# EMS_Bus.net
KiCad netlist of a schematic drawn in Altium Designer
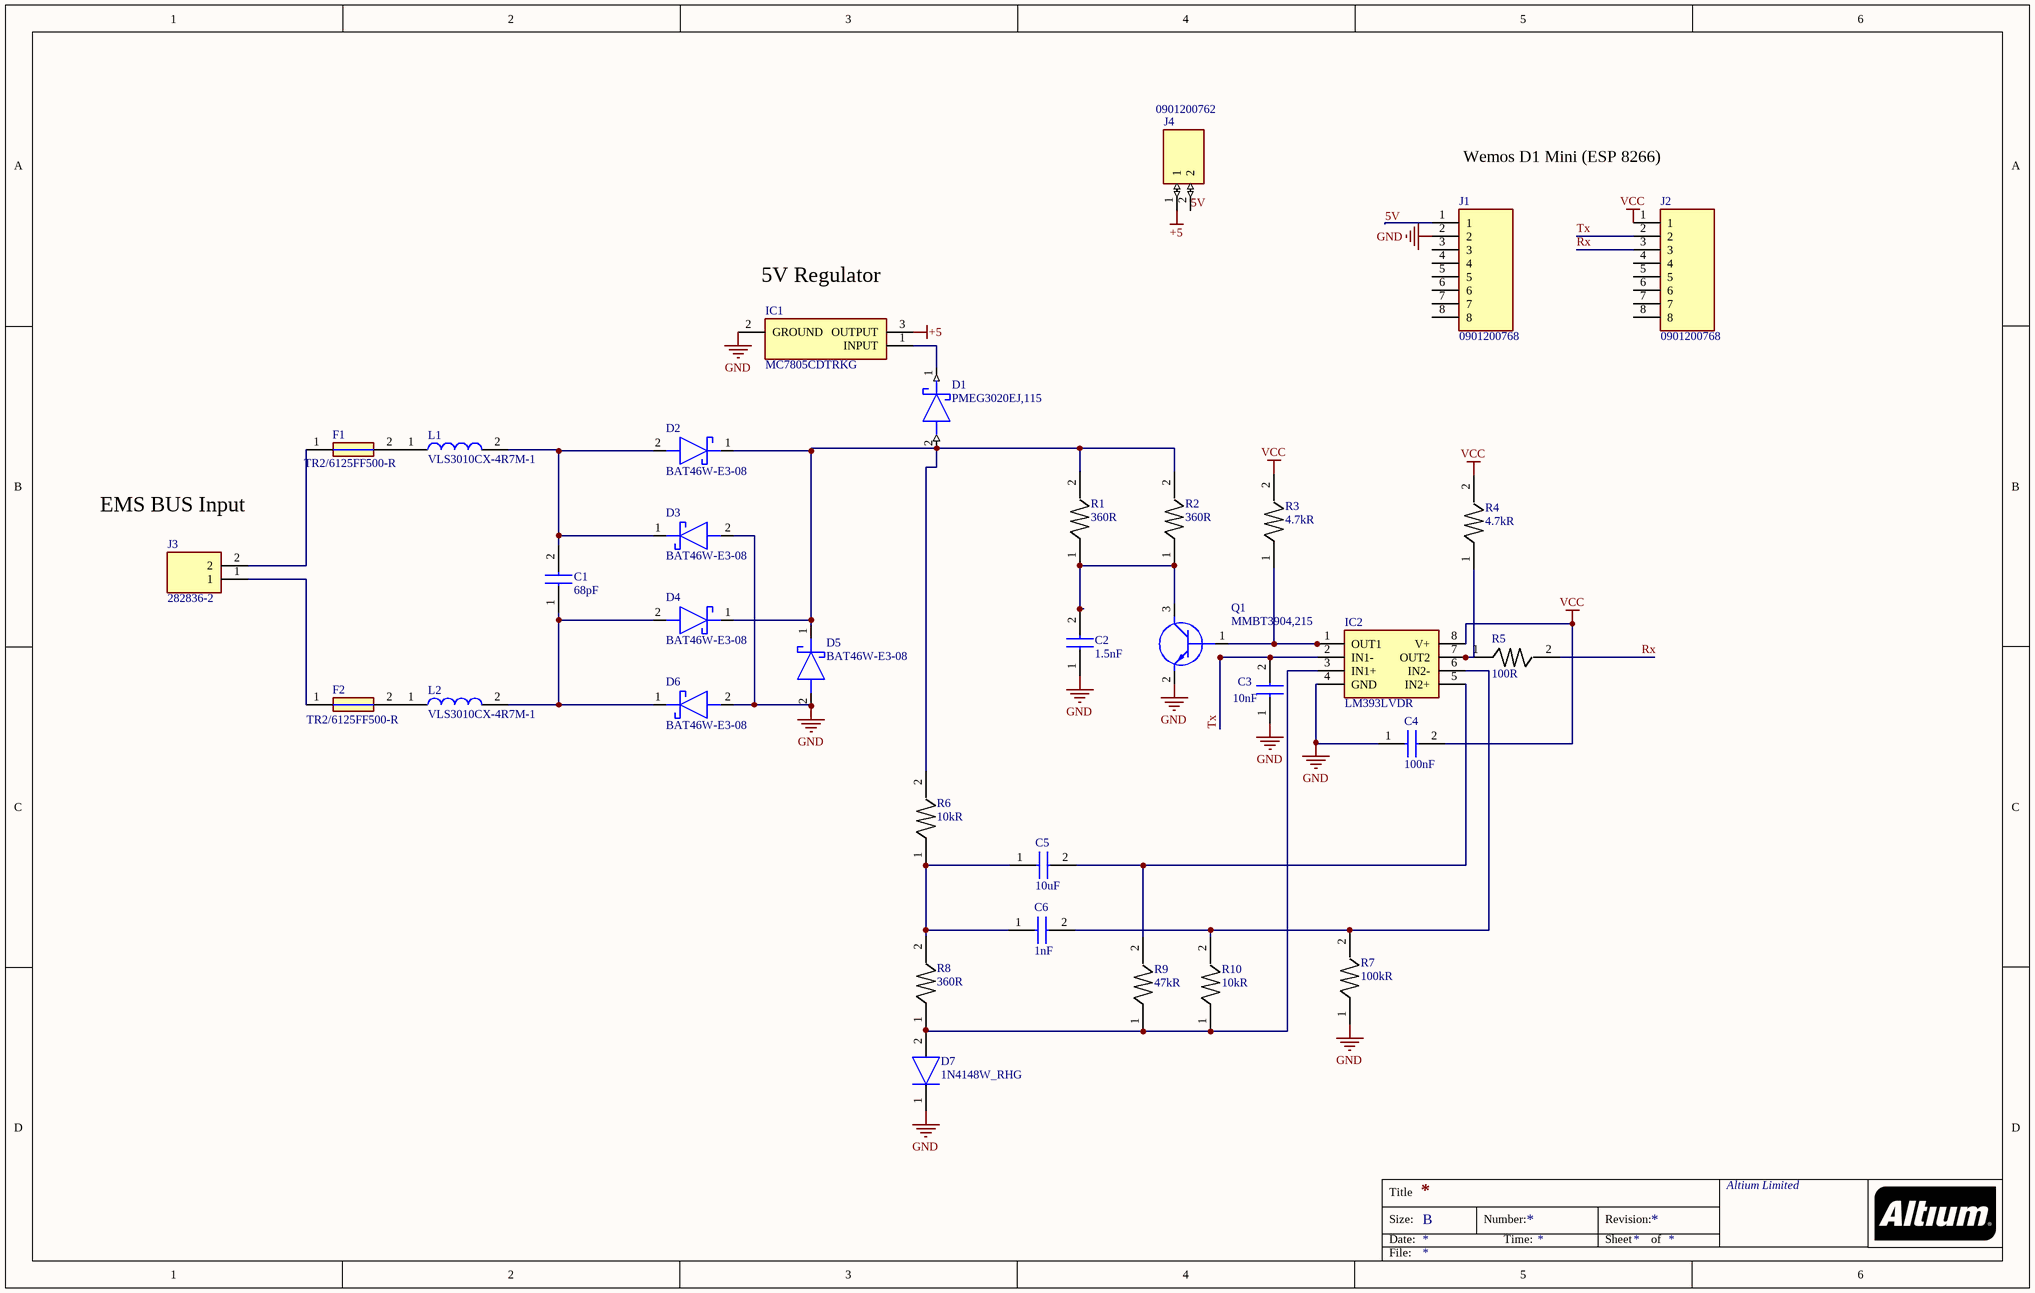
[diagram p0: EMS_Bus.SchDoc]

(export (version "E")
  (design (tool "Eeschema 10.0.6"))
  (components
    (comp (ref "C1")
      (value "885012007056")
      (footprint "SamacSys:CAPC2012X70N")
      (description "Capacitor")
      (fields
        (field (name "MANUFACTURER") "Wurth Electronics")
        (field (name "CAPACITANCE") "68pF")
        (field (name "TOLERANCE") "5%")
      )
      (libsource (lib "SamacSys") (part "885012007056"))
    )
    (comp (ref "C2")
      (value "885012207087")
      (footprint "SamacSys:CAPC2012X90N")
      (description "Capacitor")
      (fields
        (field (name "MOUSER PART NUMBER") "710-885012207087")
        (field (name "MANUFACTURER") "Wurth Electronics")
        (field (name "CAPACITANCE") "1.5nF")
      )
      (libsource (lib "SamacSys") (part "885012207087"))
    )
    (comp (ref "C3")
      (value "885012207092")
      (footprint "SamacSys:CAPC2012X90N")
      (description "Capacitor")
      (fields
        (field (name "MOUSER PART NUMBER") "710-885012207092")
        (field (name "MANUFACTURER") "Wurth Electronics")
        (field (name "CAPACITANCE") "10nF")
      )
      (libsource (lib "SamacSys") (part "885012207092"))
    )
    (comp (ref "C4")
      (value "885012207098")
      (footprint "SamacSys:CAPC2012X90N")
      (description "Capacitor")
      (fields
        (field (name "MOUSER PART NUMBER") "710-885012207098")
        (field (name "MANUFACTURER") "Wurth Electronics")
        (field (name "CAPACITANCE") "100nF")
      )
      (libsource (lib "SamacSys") (part "885012207098"))
    )
    (comp (ref "C5")
      (value "885012107014")
      (footprint "SamacSys:CAPC2012X135N")
      (description "Capacitor")
      (fields
        (field (name "MOUSER PART NUMBER") "710-885012107014")
        (field (name "MANUFACTURER") "Wurth Electronics")
        (field (name "CAPACITANCE") "10uF")
      )
      (libsource (lib "SamacSys") (part "885012107014"))
    )
    (comp (ref "C6")
      (value "885012007063")
      (footprint "SamacSys:CAPC2012X90N")
      (description "Capacitor")
      (fields
        (field (name "MOUSER PART NUMBER") "710-885012007063")
        (field (name "MANUFACTURER") "Wurth Electronics")
        (field (name "CAPACITANCE") "1nF")
      )
      (libsource (lib "SamacSys") (part "885012007063"))
    )
    (comp (ref "D1")
      (value "PMEG3020EJ,115")
      (footprint "SamacSys:SODFL2512X80N")
      (description "Schottky Diode")
      (fields (field (name "MOUSER PART NUMBER") "771-PMEG3020EJ-T/R"))
      (libsource (lib "SamacSys") (part "PMEG3020EJ,115"))
    )
    (comp (ref "D2")
      (value "BAT46W-E3-08")
      (footprint "SamacSys:SOD3716X135N")
      (description "Schottky Diode")
      (fields
        (field (name "MANUFACTURER_PART_NUMBER") "BAT46W-E3-08")
        (field (name "MOUSER PART NUMBER") "78-BAT46W-E3-08")
      )
      (libsource (lib "SamacSys") (part "BAT46W-E3-08"))
    )
    (comp (ref "D3")
      (value "BAT46W-E3-08")
      (footprint "SamacSys:SOD3716X135N")
      (description "Schottky Diode")
      (fields
        (field (name "MANUFACTURER_PART_NUMBER") "BAT46W-E3-08")
        (field (name "MOUSER PART NUMBER") "78-BAT46W-E3-08")
      )
      (libsource (lib "SamacSys") (part "BAT46W-E3-08"))
    )
    (comp (ref "D4")
      (value "BAT46W-E3-08")
      (footprint "SamacSys:SOD3716X135N")
      (description "Schottky Diode")
      (fields
        (field (name "MANUFACTURER_PART_NUMBER") "BAT46W-E3-08")
        (field (name "MOUSER PART NUMBER") "78-BAT46W-E3-08")
      )
      (libsource (lib "SamacSys") (part "BAT46W-E3-08"))
    )
    (comp (ref "D5")
      (value "BAT46W-E3-08")
      (footprint "SamacSys:SOD3716X135N")
      (description "Schottky Diode")
      (fields
        (field (name "MANUFACTURER_PART_NUMBER") "BAT46W-E3-08")
        (field (name "MOUSER PART NUMBER") "78-BAT46W-E3-08")
      )
      (libsource (lib "SamacSys") (part "BAT46W-E3-08"))
    )
    (comp (ref "D6")
      (value "BAT46W-E3-08")
      (footprint "SamacSys:SOD3716X135N")
      (description "Schottky Diode")
      (fields
        (field (name "MANUFACTURER_PART_NUMBER") "BAT46W-E3-08")
        (field (name "MOUSER PART NUMBER") "78-BAT46W-E3-08")
      )
      (libsource (lib "SamacSys") (part "BAT46W-E3-08"))
    )
    (comp (ref "D7")
      (value "1N4148W_RHG")
      (footprint "SamacSys:1N4148WRHG")
      (description "Diode")
      (fields
        (field (name "MANUFACTURER_PART_NUMBER") "1N4148W RHG")
        (field (name "MOUSER PART NUMBER") "821-1N4148WRHG")
      )
      (libsource (lib "SamacSys") (part "1N4148W_RHG"))
    )
    (comp (ref "F1")
      (value "TR2_6125FF500-R")
      (footprint "SamacSys:FUSC6127X287N")
      (description "Fuse")
      (fields
        (field (name "MANUFACTURER_PART_NUMBER") "TR2/6125FF500-R")
        (field (name "MOUSER PART NUMBER") "504-TR2/6125FF500-R")
        (field (name "MANUFACTURER PART NUMBER") "TR2/6125FF500-R")
      )
      (libsource (lib "SamacSys") (part "TR2_6125FF500-R"))
    )
    (comp (ref "F2")
      (value "TR2_6125FF500-R")
      (footprint "SamacSys:FUSC6127X287N")
      (description "Fuse")
      (fields
        (field (name "MANUFACTURER_PART_NUMBER") "TR2/6125FF500-R")
        (field (name "MOUSER PART NUMBER") "504-TR2/6125FF500-R")
        (field (name "MANUFACTURER PART NUMBER") "TR2/6125FF500-R")
      )
      (libsource (lib "SamacSys") (part "TR2_6125FF500-R"))
    )
    (comp (ref "IC1")
      (value "MC7805CDTRKG")
      (footprint "SamacSys:MJD1221G")
      (description "Integrated Circuit")
      (fields
        (field (name "MOUSER PART NUMBER") "863-MC7805CDTRKG")
        (field (name "MANUFACTURER") "ON Semiconductor")
        (field (name "MANUFACTURER PART NUMBER") "MC7805CDTRKG")
      )
      (libsource (lib "SamacSys") (part "MC7805CDTRKG"))
    )
    (comp (ref "IC2")
      (value "LM393LVDR")
      (footprint "SamacSys:SOIC127P600X175-8N")
      (description "Integrated Circuit")
      (fields
        (field (name "MOUSER PART NUMBER") "595-LM393LVDR")
        (field (name "MANUFACTURER") "Texas Instruments")
        (field (name "MANUFACTURER PART NUMBER") "LM393LVDR")
      )
      (libsource (lib "SamacSys") (part "LM393LVDR"))
    )
    (comp (ref "J1")
      (value "0901200768")
      (footprint "SamacSys:HDRV8W65P0X254_1X8_2010X249X560P")
      (description "Connector")
      (libsource (lib "SamacSys") (part "0901200768"))
    )
    (comp (ref "J2")
      (value "0901200768")
      (footprint "SamacSys:HDRV8W65P0X254_1X8_2010X249X560P")
      (description "Connector")
      (libsource (lib "SamacSys") (part "0901200768"))
    )
    (comp (ref "J3")
      (value "282836-2")
      (footprint "2828362")
      (description "Connector")
      (fields (field (name "MOUSER PART NUMBER") "571-2828362"))
      (libsource (lib "SamacSys") (part "282836-2"))
    )
    (comp (ref "J4")
      (value "0901200762")
      (footprint "SamacSys:HDRV2W65P0X254_1X2_508X254X925P")
      (description "Connector")
      (libsource (lib "SamacSys") (part "0901200762"))
    )
    (comp (ref "L1")
      (value "VLS3010CX-4R7M-1")
      (footprint "SamacSys:INDPM3030X100N")
      (description "Inductor")
      (fields
        (field (name "MOUSER PART NUMBER") "810-VLS3010CX-4R7M-1")
        (field (name "MANUFACTURER") "TDK")
        (field (name "MANUFACTURER PART NUMBER") "VLS3010CX-4R7M-1")
      )
      (libsource (lib "SamacSys") (part "VLS3010CX-4R7M-1"))
    )
    (comp (ref "L2")
      (value "VLS3010CX-4R7M-1")
      (footprint "SamacSys:INDPM3030X100N")
      (description "Inductor")
      (fields
        (field (name "MOUSER PART NUMBER") "810-VLS3010CX-4R7M-1")
        (field (name "MANUFACTURER") "TDK")
        (field (name "MANUFACTURER PART NUMBER") "VLS3010CX-4R7M-1")
      )
      (libsource (lib "SamacSys") (part "VLS3010CX-4R7M-1"))
    )
    (comp (ref "Q1")
      (value "MMBT3904,215")
      (footprint "SamacSys:SOT95P230X110-3N")
      (description "Transistor BJT NPN")
      (fields
        (field (name "MANUFACTURER_PART_NUMBER") "MMBT3904,215")
        (field (name "MOUSER PART NUMBER") "771-MMBT3904T/R")
        (field (name "MANUFACTURER") "Nexperia")
      )
      (libsource (lib "SamacSys") (part "MMBT3904,215"))
    )
    (comp (ref "R1")
      (value "RC0805FR-07360RL")
      (footprint "SamacSys:RESC2012X60N")
      (description "Resistor")
      (fields
        (field (name "MOUSER PART NUMBER") "603-RC0805FR-07360RL")
        (field (name "MANUFACTURER") "Yageo")
        (field (name "RESISTANCE") "360R")
      )
      (libsource (lib "SamacSys") (part "RC0805FR-07360RL"))
    )
    (comp (ref "R2")
      (value "RC0805FR-07360RL")
      (footprint "SamacSys:RESC2012X60N")
      (description "Resistor")
      (fields
        (field (name "MOUSER PART NUMBER") "603-RC0805FR-07360RL")
        (field (name "MANUFACTURER") "Yageo")
        (field (name "RESISTANCE") "360R")
      )
      (libsource (lib "SamacSys") (part "RC0805FR-07360RL"))
    )
    (comp (ref "R3")
      (value "RC0805FR-074K7L")
      (footprint "SamacSys:RESC2012X60N")
      (description "Resistor")
      (fields
        (field (name "MOUSER PART NUMBER") "603-RC0805FR-074K7L")
        (field (name "MANUFACTURER") "Yageo")
        (field (name "RESISTANCE") "4.7kR")
      )
      (libsource (lib "SamacSys") (part "RC0805FR-074K7L"))
    )
    (comp (ref "R4")
      (value "RC0805FR-074K7L")
      (footprint "SamacSys:RESC2012X60N")
      (description "Resistor")
      (fields
        (field (name "MOUSER PART NUMBER") "603-RC0805FR-074K7L")
        (field (name "MANUFACTURER") "Yageo")
        (field (name "RESISTANCE") "4.7kR")
      )
      (libsource (lib "SamacSys") (part "RC0805FR-074K7L"))
    )
    (comp (ref "R5")
      (value "RC0805FR-07100RL")
      (footprint "SamacSys:RESC2012X60N")
      (description "Resistor")
      (fields
        (field (name "MOUSER PART NUMBER") "603-RC0805FR-07100RL")
        (field (name "MANUFACTURER") "Yageo")
        (field (name "RESISTANCE") "100R")
      )
      (libsource (lib "SamacSys") (part "RC0805FR-07100RL"))
    )
    (comp (ref "R6")
      (value "RT0805FRE0710KL")
      (footprint "SamacSys:RESC2012X60N")
      (description "Resistor")
      (fields
        (field (name "MOUSER PART NUMBER") "603-RT0805FRE0710KL")
        (field (name "MANUFACTURER") "Yageo")
        (field (name "RESISTANCE") "10kR")
      )
      (libsource (lib "SamacSys") (part "RT0805FRE0710KL"))
    )
    (comp (ref "R7")
      (value "RC0805FR-07100KL")
      (footprint "SamacSys:RESC2012X60N")
      (description "Resistor")
      (fields
        (field (name "MOUSER PART NUMBER") "603-RC0805FR-07100KL")
        (field (name "MANUFACTURER") "Yageo")
        (field (name "RESISTANCE") "100kR")
      )
      (libsource (lib "SamacSys") (part "RC0805FR-07100KL"))
    )
    (comp (ref "R8")
      (value "RC0805FR-07360RL")
      (footprint "SamacSys:RESC2012X60N")
      (description "Resistor")
      (fields
        (field (name "MOUSER PART NUMBER") "603-RC0805FR-07360RL")
        (field (name "MANUFACTURER") "Yageo")
        (field (name "RESISTANCE") "360R")
      )
      (libsource (lib "SamacSys") (part "RC0805FR-07360RL"))
    )
    (comp (ref "R9")
      (value "RT0805FRE0747KL")
      (footprint "SamacSys:RESC2012X60N")
      (description "Resistor")
      (fields
        (field (name "MOUSER PART NUMBER") "603-RT0805FRE0747KL")
        (field (name "MANUFACTURER") "Yageo")
        (field (name "RESISTANCE") "47kR")
      )
      (libsource (lib "SamacSys") (part "RT0805FRE0747KL"))
    )
    (comp (ref "R10")
      (value "RT0805FRE0710KL")
      (footprint "SamacSys:RESC2012X60N")
      (description "Resistor")
      (fields
        (field (name "MOUSER PART NUMBER") "603-RT0805FRE0710KL")
        (field (name "MANUFACTURER") "Yageo")
        (field (name "RESISTANCE") "10kR")
      )
      (libsource (lib "SamacSys") (part "RT0805FRE0710KL"))
    )
  )
  (nets
    (net (code "1") (name "+5") (class "Default")
      (node (ref "IC1") (pin "3") (pinfunction "OUTPUT_3") (pintype "passive"))
      (node (ref "J4") (pin "1") (pinfunction "1_1") (pintype "bidirectional"))
    )
    (net (code "2") (name "/5V") (class "Default")
      (node (ref "J1") (pin "1") (pinfunction "1_1") (pintype "passive"))
      (node (ref "J4") (pin "2") (pinfunction "2_2") (pintype "bidirectional"))
    )
    (net (code "3") (name "/Rx") (class "Default")
      (node (ref "J2") (pin "3") (pinfunction "3_3") (pintype "passive"))
      (node (ref "R5") (pin "2") (pinfunction "2_2") (pintype "passive"))
    )
    (net (code "4") (name "/Tx") (class "Default")
      (node (ref "C3") (pin "2") (pinfunction "2_2") (pintype "passive"))
      (node (ref "IC2") (pin "2") (pinfunction "IN1-_2") (pintype "passive"))
      (node (ref "J2") (pin "2") (pinfunction "2_2") (pintype "passive"))
    )
    (net (code "5") (name "GND") (class "Default")
      (node (ref "C2") (pin "1") (pinfunction "1_1") (pintype "passive"))
      (node (ref "C3") (pin "1") (pinfunction "1_1") (pintype "passive"))
      (node (ref "C4") (pin "1") (pinfunction "1_1") (pintype "passive"))
      (node (ref "D3") (pin "2") (pinfunction "A_2") (pintype "passive"))
      (node (ref "D5") (pin "2") (pinfunction "A_2") (pintype "passive"))
      (node (ref "D6") (pin "2") (pinfunction "A_2") (pintype "passive"))
      (node (ref "D7") (pin "1") (pinfunction "K_1") (pintype "passive"))
      (node (ref "IC1") (pin "2") (pinfunction "GROUND_2") (pintype "passive"))
      (node (ref "IC2") (pin "4") (pinfunction "GND_4") (pintype "passive"))
      (node (ref "J1") (pin "2") (pinfunction "2_2") (pintype "passive"))
      (node (ref "Q1") (pin "2") (pinfunction "E_2") (pintype "passive"))
      (node (ref "R7") (pin "1") (pinfunction "1_1") (pintype "passive"))
    )
    (net (code "6") (name "Net-(C5-Pad1)") (class "Default")
      (node (ref "C5") (pin "1") (pinfunction "1_1") (pintype "passive"))
      (node (ref "C6") (pin "1") (pinfunction "1_1") (pintype "passive"))
      (node (ref "R6") (pin "1") (pinfunction "1_1") (pintype "passive"))
      (node (ref "R8") (pin "2") (pinfunction "2_2") (pintype "passive"))
    )
    (net (code "7") (name "Net-(D1-A)") (class "Default")
      (node (ref "D1") (pin "2") (pinfunction "A_2") (pintype "input"))
      (node (ref "D2") (pin "1") (pinfunction "K_1") (pintype "passive"))
      (node (ref "D4") (pin "1") (pinfunction "K_1") (pintype "passive"))
      (node (ref "D5") (pin "1") (pinfunction "K_1") (pintype "passive"))
      (node (ref "R1") (pin "2") (pinfunction "2_2") (pintype "passive"))
      (node (ref "R2") (pin "2") (pinfunction "2_2") (pintype "passive"))
      (node (ref "R6") (pin "2") (pinfunction "2_2") (pintype "passive"))
    )
    (net (code "8") (name "Net-(D1-K)") (class "Default")
      (node (ref "D1") (pin "1") (pinfunction "K_1") (pintype "output"))
      (node (ref "IC1") (pin "1") (pinfunction "INPUT_1") (pintype "passive"))
    )
    (net (code "9") (name "Net-(D2-A)") (class "Default")
      (node (ref "C1") (pin "2") (pinfunction "2_2") (pintype "passive"))
      (node (ref "D2") (pin "2") (pinfunction "A_2") (pintype "passive"))
      (node (ref "D3") (pin "1") (pinfunction "K_1") (pintype "passive"))
      (node (ref "L1") (pin "2") (pinfunction "2_2") (pintype "passive"))
    )
    (net (code "10") (name "Net-(D4-A)") (class "Default")
      (node (ref "C1") (pin "1") (pinfunction "1_1") (pintype "passive"))
      (node (ref "D4") (pin "2") (pinfunction "A_2") (pintype "passive"))
      (node (ref "D6") (pin "1") (pinfunction "K_1") (pintype "passive"))
      (node (ref "L2") (pin "2") (pinfunction "2_2") (pintype "passive"))
    )
    (net (code "11") (name "Net-(D7-A)") (class "Default")
      (node (ref "D7") (pin "2") (pinfunction "A_2") (pintype "passive"))
      (node (ref "IC2") (pin "3") (pinfunction "IN1+_3") (pintype "passive"))
      (node (ref "R10") (pin "1") (pinfunction "1_1") (pintype "passive"))
      (node (ref "R8") (pin "1") (pinfunction "1_1") (pintype "passive"))
      (node (ref "R9") (pin "1") (pinfunction "1_1") (pintype "passive"))
    )
    (net (code "12") (name "Net-(F1-Pad1)") (class "Default")
      (node (ref "F1") (pin "1") (pinfunction "1_1") (pintype "passive"))
      (node (ref "J3") (pin "2") (pinfunction "2_2") (pintype "passive"))
    )
    (net (code "13") (name "Net-(F1-Pad2)") (class "Default")
      (node (ref "F1") (pin "2") (pinfunction "2_2") (pintype "passive"))
      (node (ref "L1") (pin "1") (pinfunction "1_1") (pintype "passive"))
    )
    (net (code "14") (name "Net-(F2-Pad1)") (class "Default")
      (node (ref "F2") (pin "1") (pinfunction "1_1") (pintype "passive"))
      (node (ref "J3") (pin "1") (pinfunction "1_1") (pintype "passive"))
    )
    (net (code "15") (name "Net-(F2-Pad2)") (class "Default")
      (node (ref "F2") (pin "2") (pinfunction "2_2") (pintype "passive"))
      (node (ref "L2") (pin "1") (pinfunction "1_1") (pintype "passive"))
    )
    (net (code "16") (name "Net-(IC2-IN2+)") (class "Default")
      (node (ref "C5") (pin "2") (pinfunction "2_2") (pintype "passive"))
      (node (ref "IC2") (pin "5") (pinfunction "IN2+_5") (pintype "passive"))
      (node (ref "R9") (pin "2") (pinfunction "2_2") (pintype "passive"))
    )
    (net (code "17") (name "Net-(IC2-IN2-)") (class "Default")
      (node (ref "C6") (pin "2") (pinfunction "2_2") (pintype "passive"))
      (node (ref "IC2") (pin "6") (pinfunction "IN2-_6") (pintype "passive"))
      (node (ref "R10") (pin "2") (pinfunction "2_2") (pintype "passive"))
      (node (ref "R7") (pin "2") (pinfunction "2_2") (pintype "passive"))
    )
    (net (code "18") (name "Net-(IC2-OUT1)") (class "Default")
      (node (ref "IC2") (pin "1") (pinfunction "OUT1_1") (pintype "passive"))
      (node (ref "Q1") (pin "1") (pinfunction "B_1") (pintype "passive"))
      (node (ref "R3") (pin "1") (pinfunction "1_1") (pintype "passive"))
    )
    (net (code "19") (name "Net-(IC2-OUT2)") (class "Default")
      (node (ref "IC2") (pin "7") (pinfunction "OUT2_7") (pintype "passive"))
      (node (ref "R4") (pin "1") (pinfunction "1_1") (pintype "passive"))
      (node (ref "R5") (pin "1") (pinfunction "1_1") (pintype "passive"))
    )
    (net (code "20") (name "Net-(Q1-C)") (class "Default")
      (node (ref "C2") (pin "2") (pinfunction "2_2") (pintype "passive"))
      (node (ref "Q1") (pin "3") (pinfunction "C_3") (pintype "passive"))
      (node (ref "R1") (pin "1") (pinfunction "1_1") (pintype "passive"))
      (node (ref "R2") (pin "1") (pinfunction "1_1") (pintype "passive"))
    )
    (net (code "21") (name "VCC") (class "Default")
      (node (ref "C4") (pin "2") (pinfunction "2_2") (pintype "passive"))
      (node (ref "IC2") (pin "8") (pinfunction "V+_8") (pintype "passive"))
      (node (ref "J2") (pin "1") (pinfunction "1_1") (pintype "passive"))
      (node (ref "R3") (pin "2") (pinfunction "2_2") (pintype "passive"))
      (node (ref "R4") (pin "2") (pinfunction "2_2") (pintype "passive"))
    )
    (net (code "22") (name "unconnected-(J1-Pad3)") (class "Default")
      (node (ref "J1") (pin "3") (pinfunction "3_3") (pintype "passive"))
    )
    (net (code "23") (name "unconnected-(J1-Pad4)") (class "Default")
      (node (ref "J1") (pin "4") (pinfunction "4_4") (pintype "passive"))
    )
    (net (code "24") (name "unconnected-(J1-Pad5)") (class "Default")
      (node (ref "J1") (pin "5") (pinfunction "5_5") (pintype "passive"))
    )
    (net (code "25") (name "unconnected-(J1-Pad6)") (class "Default")
      (node (ref "J1") (pin "6") (pinfunction "6_6") (pintype "passive"))
    )
    (net (code "26") (name "unconnected-(J1-Pad7)") (class "Default")
      (node (ref "J1") (pin "7") (pinfunction "7_7") (pintype "passive"))
    )
    (net (code "27") (name "unconnected-(J1-Pad8)") (class "Default")
      (node (ref "J1") (pin "8") (pinfunction "8_8") (pintype "passive"))
    )
    (net (code "28") (name "unconnected-(J2-Pad4)") (class "Default")
      (node (ref "J2") (pin "4") (pinfunction "4_4") (pintype "passive"))
    )
    (net (code "29") (name "unconnected-(J2-Pad5)") (class "Default")
      (node (ref "J2") (pin "5") (pinfunction "5_5") (pintype "passive"))
    )
    (net (code "30") (name "unconnected-(J2-Pad6)") (class "Default")
      (node (ref "J2") (pin "6") (pinfunction "6_6") (pintype "passive"))
    )
    (net (code "31") (name "unconnected-(J2-Pad7)") (class "Default")
      (node (ref "J2") (pin "7") (pinfunction "7_7") (pintype "passive"))
    )
    (net (code "32") (name "unconnected-(J2-Pad8)") (class "Default")
      (node (ref "J2") (pin "8") (pinfunction "8_8") (pintype "passive"))
    )
  )
)
